# Sensor_Board.net
KiCad netlist of a schematic drawn in Altium Designer
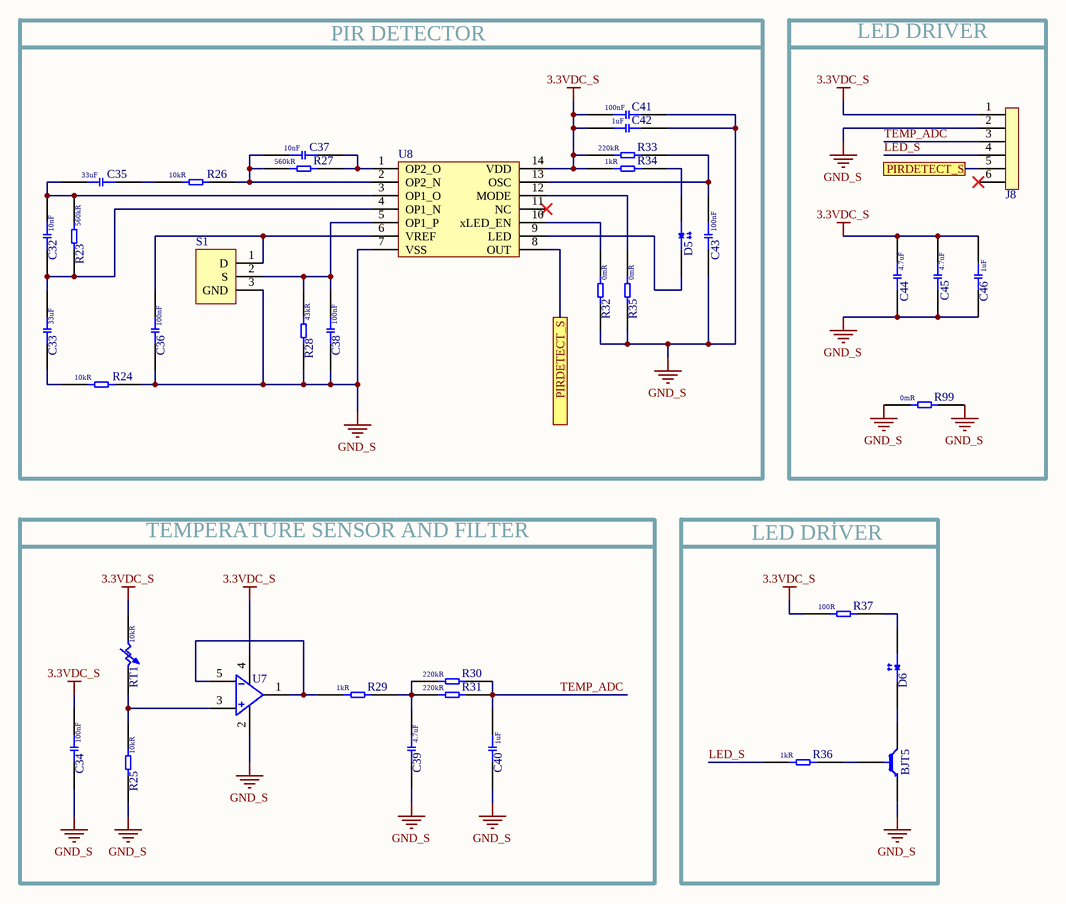
[diagram p0: Sensor Board.SchDoc]

(export (version "E")
  (design (tool "Eeschema 10.0.6"))
  (components
    (comp (ref "BJT5")
      (value "MMBT3904-7-F")
      (footprint "SOT-23F")
      (description "TRANS NPN 40V 0.2A SMD SOT23-3")
      (fields (field (name "MANUFACTURER") "Diodes Zetex") (field (name "DESIGNED BY") "M.C"))
      (libsource (lib "HedefPro_Library") (part "MMBT3904-7-F"))
    )
    (comp (ref "C32")
      (value "0603B103K500CT")
      (footprint "CAP_0603")
      (description "WALSIN - 0603B103K500CT - CAP, 0.01µF, 50V, 10%, X7R, 0603")
      (fields
        (field (name "MANUFACTURER") "Walsin Technologies")
        (field (name "TOLERANCE") "10%")
        (field (name "CAPACITANCE") "10nF")
        (field (name "DESIGNED BY") "M.C")
      )
      (libsource (lib "HedefPro_Library") (part "CAP 10nF 0603"))
    )
    (comp (ref "C33")
      (value "C3216X5R1E336M160AC")
      (footprint "CAP_1206")
      (description "Cap Ceramic 33uF 25V X5R 20% SMD 1206 85C T/R")
      (fields
        (field (name "MANUFACTURER") "TDK")
        (field (name "TOLERANCE") "20%")
        (field (name "CAPACITANCE") "33uF")
        (field (name "DESIGNED BY") "M.C")
      )
      (libsource (lib "HedefPro_Library") (part "CAP  33uF 1206"))
    )
    (comp (ref "C34")
      (value "C0603C104K5RACTU")
      (footprint "CAP_0603")
      (description "Multilayer Ceramic Capacitors (MLCC) - SMD/SMT 50volts 0.1uF X7R 10%")
      (fields
        (field (name "MANUFACTURER") "KEMET")
        (field (name "TOLERANCE") "10%")
        (field (name "CAPACITANCE") "100nF")
        (field (name "DESIGNED BY") "M.C")
      )
      (libsource (lib "HedefPro_Library") (part "CAP 100nF 0603"))
    )
    (comp (ref "C35")
      (value "C3216X5R1E336M160AC")
      (footprint "CAP_1206")
      (description "Cap Ceramic 33uF 25V X5R 20% SMD 1206 85C T/R")
      (fields
        (field (name "MANUFACTURER") "TDK")
        (field (name "TOLERANCE") "20%")
        (field (name "CAPACITANCE") "33uF")
        (field (name "DESIGNED BY") "M.C")
      )
      (libsource (lib "HedefPro_Library") (part "CAP  33uF 1206"))
    )
    (comp (ref "C36")
      (value "ALA7DF471CF450")
      (footprint "CAP_0603")
      (description "CAP CER 100nF %10 0603 SMD")
      (fields
        (field (name "MANUFACTURER") "KEMET")
        (field (name "CAPATICANTE") "100nF")
        (field (name "DESIGNED BY") "M.C")
      )
      (libsource (lib "HedefPro_Library") (part "CAP 100nf 0603_1"))
    )
    (comp (ref "C37")
      (value "0603B103K500CT")
      (footprint "CAP_0603")
      (description "WALSIN - 0603B103K500CT - CAP, 0.01µF, 50V, 10%, X7R, 0603")
      (fields
        (field (name "MANUFACTURER") "Walsin Technologies")
        (field (name "TOLERANCE") "10%")
        (field (name "CAPACITANCE") "10nF")
        (field (name "DESIGNED BY") "M.C")
      )
      (libsource (lib "HedefPro_Library") (part "CAP 10nF 0603"))
    )
    (comp (ref "C38")
      (value "ALA7DF471CF450")
      (footprint "CAP_0603")
      (description "CAP CER 100nF %10 0603 SMD")
      (fields
        (field (name "MANUFACTURER") "KEMET")
        (field (name "CAPATICANTE") "100nF")
        (field (name "DESIGNED BY") "M.C")
      )
      (libsource (lib "HedefPro_Library") (part "CAP 100nf 0603_1"))
    )
    (comp (ref "C39")
      (value "CL21A475KAQNNNE")
      (footprint "CAP_0805")
      (fields
        (field (name "MANUFACTURER") "Samsung")
        (field (name "TOLERANCE") "10%")
        (field (name "CAPACITANCE") "4.7uF")
        (field (name "DESIGNED BY") "M.C")
      )
      (libsource (lib "HedefPro_Library") (part "CAP 4.7uF 0805"))
    )
    (comp (ref "C40")
      (value "CL21B105KBFNNNE")
      (footprint "CAP_0805")
      (fields
        (field (name "MANUFACTURER") "Samsung")
        (field (name "TOLERANCE") "10%")
        (field (name "VOLTAGE") "50V")
        (field (name "CAPACITANCE") "1uF")
        (field (name "DESIGNED BY") "M.C")
      )
      (libsource (lib "HedefPro_Library") (part "CAP 1uF 0805"))
    )
    (comp (ref "C41")
      (value "ALA7DF471CF450")
      (footprint "CAP_0603")
      (description "CAP CER 100nF %10 0603 SMD")
      (fields
        (field (name "MANUFACTURER") "KEMET")
        (field (name "CAPATICANTE") "100nF")
        (field (name "DESIGNED BY") "M.C")
      )
      (libsource (lib "HedefPro_Library") (part "CAP 100nf 0603_1"))
    )
    (comp (ref "C42")
      (value "CL21B105KBFNNNE")
      (footprint "CAP_0805")
      (fields
        (field (name "MANUFACTURER") "Samsung")
        (field (name "TOLERANCE") "10%")
        (field (name "VOLTAGE") "50V")
        (field (name "CAPACITANCE") "1uF")
        (field (name "DESIGNED BY") "M.C")
      )
      (libsource (lib "HedefPro_Library") (part "CAP 1uF 0805"))
    )
    (comp (ref "C43")
      (value "ALA7DF471CF450")
      (footprint "CAP_0603")
      (description "CAP CER 100nF %10 0603 SMD")
      (fields
        (field (name "MANUFACTURER") "KEMET")
        (field (name "CAPATICANTE") "100nF")
        (field (name "DESIGNED BY") "M.C")
      )
      (libsource (lib "HedefPro_Library") (part "CAP 100nf 0603_1"))
    )
    (comp (ref "C44")
      (value "CL21A475KAQNNNE")
      (footprint "CAP_0805")
      (fields
        (field (name "MANUFACTURER") "Samsung")
        (field (name "TOLERANCE") "10%")
        (field (name "CAPACITANCE") "4.7uF")
        (field (name "DESIGNED BY") "M.C")
      )
      (libsource (lib "HedefPro_Library") (part "CAP 4.7uF 0805"))
    )
    (comp (ref "C45")
      (value "CL21A475KAQNNNE")
      (footprint "CAP_0805")
      (fields
        (field (name "MANUFACTURER") "Samsung")
        (field (name "TOLERANCE") "10%")
        (field (name "CAPACITANCE") "4.7uF")
        (field (name "DESIGNED BY") "M.C")
      )
      (libsource (lib "HedefPro_Library") (part "CAP 4.7uF 0805"))
    )
    (comp (ref "C46")
      (value "CL21B105KBFNNNE")
      (footprint "CAP_0805")
      (fields
        (field (name "MANUFACTURER") "Samsung")
        (field (name "TOLERANCE") "10%")
        (field (name "VOLTAGE") "50V")
        (field (name "CAPACITANCE") "1uF")
        (field (name "DESIGNED BY") "M.C")
      )
      (libsource (lib "HedefPro_Library") (part "CAP 1uF 0805"))
    )
    (comp (ref "D5")
      (value "LTST-C171GKT")
      (footprint "LED_0805_GREEN")
      (description "Green 0805 130 º Min 5 mcd Typical 12 mcd Water Clear Lens SMT LED")
      (fields (field (name "MANUFACTURER") "Vishay Lite-On") (field (name "DESIGNED BY") "M.C"))
      (libsource (lib "HedefPro_Library") (part "LTST-C171GKT"))
    )
    (comp (ref "D6")
      (value "LH R974-LP-1-0-20-R18")
      (footprint "LED_0805_RED")
      (description "Single Color LED, Hyper Red, Colorless Diffused, 1.3mm")
      (fields
        (field (name "MANUFACTURER") "Osram Opto")
        (field (name "MANUFACTURER PART NUMBER") "LHR974-LP-1-0-20-R18")
        (field (name "DESIGNED BY") "M.C")
      )
      (libsource (lib "HedefPro_Library") (part "LH R974-LP-1-0-20-R18"))
    )
    (comp (ref "J8")
      (value "64800611622")
      (footprint "64800611622")
      (description "1.50mm 6PIN Connector")
      (fields (field (name "MANUFACTURER") "Wurth Electronics") (field (name "DESIGNED BY") "M.C"))
      (libsource (lib "HedefPro_Library") (part "64800611622"))
    )
    (comp (ref "R23")
      (value "RC0603JR-07560KL")
      (footprint "RES_0603")
      (description "RES SMD 560K OHM 5% 1/10W 0603")
      (fields
        (field (name "MANUFACTURER") "Yageo")
        (field (name "TOLERANCE") "5%")
        (field (name "RESISTANCE") "560kR")
        (field (name "DESIGNED BY") "M.C")
      )
      (libsource (lib "HedefPro_Library") (part "RES 560kR OHM 0603"))
    )
    (comp (ref "R24")
      (value "RC0201FR-0710KL")
      (footprint "RES_0603")
      (description "GENERAL 0201 11% REEL (7INCH)")
      (fields
        (field (name "MANUFACTURER") "Yageo")
        (field (name "TOLERANCE") "1%")
        (field (name "RESISTANCE") "10kR")
        (field (name "DESIGNED BY") "M.C")
      )
      (libsource (lib "HedefPro_Library") (part "RES 10K OHM 0603"))
    )
    (comp (ref "R25")
      (value "RC0201FR-0710KL")
      (footprint "RES_0603")
      (description "GENERAL 0201 11% REEL (7INCH)")
      (fields
        (field (name "MANUFACTURER") "Yageo")
        (field (name "TOLERANCE") "1%")
        (field (name "RESISTANCE") "10kR")
        (field (name "DESIGNED BY") "M.C")
      )
      (libsource (lib "HedefPro_Library") (part "RES 10K OHM 0603"))
    )
    (comp (ref "R26")
      (value "RC0201FR-0710KL")
      (footprint "RES_0603")
      (description "GENERAL 0201 11% REEL (7INCH)")
      (fields
        (field (name "MANUFACTURER") "Yageo")
        (field (name "TOLERANCE") "1%")
        (field (name "RESISTANCE") "10kR")
        (field (name "DESIGNED BY") "M.C")
      )
      (libsource (lib "HedefPro_Library") (part "RES 10K OHM 0603"))
    )
    (comp (ref "R27")
      (value "RC0603JR-07560KL")
      (footprint "RES_0603")
      (description "RES SMD 560K OHM 5% 1/10W 0603")
      (fields
        (field (name "MANUFACTURER") "Yageo")
        (field (name "TOLERANCE") "5%")
        (field (name "RESISTANCE") "560kR")
        (field (name "DESIGNED BY") "M.C")
      )
      (libsource (lib "HedefPro_Library") (part "RES 560kR OHM 0603"))
    )
    (comp (ref "R28")
      (value "RC0603JR-0743KL")
      (footprint "RES_0603")
      (fields
        (field (name "MANUFACTURER") "Yageo")
        (field (name "TOLERANCE") "5%")
        (field (name "RESISTANCE") "43kR")
        (field (name "DESIGNED BY") "M.C")
      )
      (libsource (lib "HedefPro_Library") (part "RES 43kR OHM 0603"))
    )
    (comp (ref "R29")
      (value "RC0603FR-101KL")
      (footprint "RES_0603")
      (description "Res Thick Film 0603 1K Ohm 1% 0.1W(1/10W) ±100ppm/C Pad SMD T/R")
      (fields
        (field (name "MANUFACTURER") "Yageo")
        (field (name "TOLERANCE") "1%")
        (field (name "RESISTANCE") "1kR")
        (field (name "DESIGNED BY") "M.C")
      )
      (libsource (lib "HedefPro_Library") (part "RES 1kR OHM 0603"))
    )
    (comp (ref "R30")
      (value "RC0603JR-07220KL")
      (footprint "RES_0603")
      (fields
        (field (name "MANUFACTURER") "Yageo")
        (field (name "TOLERANCE") "5%")
        (field (name "RESISTANCE") "220kR")
        (field (name "DESIGNED BY") "M.C")
      )
      (libsource (lib "HedefPro_Library") (part "RES 220kR OHM 0603"))
    )
    (comp (ref "R31")
      (value "RC0603JR-07220KL")
      (footprint "RES_0603")
      (fields
        (field (name "MANUFACTURER") "Yageo")
        (field (name "TOLERANCE") "5%")
        (field (name "RESISTANCE") "220kR")
        (field (name "DESIGNED BY") "M.C")
      )
      (libsource (lib "HedefPro_Library") (part "RES 220kR OHM 0603"))
    )
    (comp (ref "R32")
      (value "RC0603JR-070RL")
      (footprint "RES_0603")
      (description "RES SMD 0 OHM JUMPER 1/10W 0603")
      (fields
        (field (name "MANUFACTURER") "Yageo")
        (field (name "TOLERANCE") "1%")
        (field (name "RESISTANCE") "0mR")
        (field (name "DESIGNED BY") "M.C")
      )
      (libsource (lib "HedefPro_Library") (part "RES 0mR OHM 0603"))
    )
    (comp (ref "R33")
      (value "RC0603JR-07220KL")
      (footprint "RES_0603")
      (fields
        (field (name "MANUFACTURER") "Yageo")
        (field (name "TOLERANCE") "5%")
        (field (name "RESISTANCE") "220kR")
        (field (name "DESIGNED BY") "M.C")
      )
      (libsource (lib "HedefPro_Library") (part "RES 220kR OHM 0603"))
    )
    (comp (ref "R34")
      (value "RC0603FR-101KL")
      (footprint "RES_0603")
      (description "Res Thick Film 0603 1K Ohm 1% 0.1W(1/10W) ±100ppm/C Pad SMD T/R")
      (fields
        (field (name "MANUFACTURER") "Yageo")
        (field (name "TOLERANCE") "1%")
        (field (name "RESISTANCE") "1kR")
        (field (name "DESIGNED BY") "M.C")
      )
      (libsource (lib "HedefPro_Library") (part "RES 1kR OHM 0603"))
    )
    (comp (ref "R35")
      (value "RC0603JR-070RL")
      (footprint "RES_0603")
      (description "RES SMD 0 OHM JUMPER 1/10W 0603")
      (fields
        (field (name "MANUFACTURER") "Yageo")
        (field (name "TOLERANCE") "1%")
        (field (name "RESISTANCE") "0mR")
        (field (name "DESIGNED BY") "M.C")
      )
      (libsource (lib "HedefPro_Library") (part "RES 0mR OHM 0603"))
    )
    (comp (ref "R36")
      (value "RC0603FR-101KL")
      (footprint "RES_0603")
      (description "Res Thick Film 0603 1K Ohm 1% 0.1W(1/10W) ±100ppm/C Pad SMD T/R")
      (fields
        (field (name "MANUFACTURER") "Yageo")
        (field (name "TOLERANCE") "1%")
        (field (name "RESISTANCE") "1kR")
        (field (name "DESIGNED BY") "M.C")
      )
      (libsource (lib "HedefPro_Library") (part "RES 1kR OHM 0603"))
    )
    (comp (ref "R37")
      (value "RC0603JR-07100RL")
      (footprint "RES_0603")
      (description "Res Thick Film 0603 100 Ohm 5% 0.1W(1/10W) ±100ppm/C Molded SMD Paper T/R")
      (fields
        (field (name "MANUFACTURER") "Yageo")
        (field (name "TOLERANCE") "5%")
        (field (name "RESISTANCE") "100R")
        (field (name "DESIGNED BY") "M.C")
      )
      (libsource (lib "HedefPro_Library") (part "RES 100R OHM 0603"))
    )
    (comp (ref "R99")
      (value "RC0603JR-070RL")
      (footprint "RES_0603")
      (description "RES SMD 0 OHM JUMPER 1/10W 0603")
      (fields
        (field (name "MANUFACTURER") "Yageo")
        (field (name "TOLERANCE") "1%")
        (field (name "RESISTANCE") "0mR")
        (field (name "DESIGNED BY") "M.C")
      )
      (libsource (lib "HedefPro_Library") (part "RES 0mR OHM 0603"))
    )
    (comp (ref "RT1")
      (value "TFPT1206L1002FM")
      (footprint "RES_1206")
      (description "Thermistor PTC 10K Ohm 1% 2-Pin 1206 Surface Mount Solder Pad T/R Automotive")
      (fields
        (field (name "MANUFACTURER") "Vishay Dale")
        (field (name "TOLERANCE") "1%")
        (field (name "RESISTANCE") "10kR")
        (field (name "DESIGNED BY") "M.C")
      )
      (libsource (lib "HedefPro_Library") (part "TFPT1206L1002FM"))
    )
    (comp (ref "S1")
      (value "LHI 878/3902")
      (footprint "LHI 878/3902 - PYD 1388 / 708")
      (description "PYD 1388 / 7083 SENSOR PYRO DETECTOR DUAL MOTION")
      (fields
        (field (name "MANUFACTURER") "Excelitas")
        (field (name "MANUFACTURER PART NUMBER") "LHI878/3902")
        (field (name "DESIGNED BY") "M.C")
      )
      (libsource (lib "HedefPro_Library") (part "LHI 878/3902"))
    )
    (comp (ref "U7")
      (value "OPA314AIDBVR")
      (footprint "SOT23-5")
      (description "Op Amp")
      (fields (field (name "MANUFACTURER") "Texas Instruments") (field (name "DESIGNED BY") "M.C"))
      (libsource (lib "HedefPro_Library") (part "OPA314AIDBVR"))
    )
    (comp (ref "U8")
      (value "NCS36000DRG")
      (footprint "SOIC14")
      (description "Low Noise Amplifiers and LDO Regulator 14-Pin SOIC N T/R")
      (fields (field (name "MANUFACTURER") "ON Semiconductor") (field (name "DESIGNED BY") "M.C"))
      (libsource (lib "HedefPro_Library") (part "NCS36000DRG"))
    )
  )
  (nets
    (net (code "1") (name "/LED_S") (class "Default")
      (node (ref "J8") (pin "4") (pinfunction "4_4") (pintype "passive"))
      (node (ref "R36") (pin "1") (pinfunction "1_1") (pintype "passive"))
    )
    (net (code "2") (name "/PIRDETECT_S") (class "Default")
      (node (ref "J8") (pin "5") (pinfunction "5_5") (pintype "passive"))
      (node (ref "U8") (pin "8") (pinfunction "OUT_8") (pintype "passive"))
    )
    (net (code "3") (name "/TEMP_ADC") (class "Default")
      (node (ref "C40") (pin "2") (pinfunction "2_2") (pintype "passive"))
      (node (ref "J8") (pin "3") (pinfunction "3_3") (pintype "passive"))
      (node (ref "R30") (pin "2") (pinfunction "2_2") (pintype "passive"))
      (node (ref "R31") (pin "2") (pinfunction "2_2") (pintype "passive"))
    )
    (net (code "4") (name "3.3VDC_S") (class "Default")
      (node (ref "C34") (pin "2") (pinfunction "2_2") (pintype "passive"))
      (node (ref "C41") (pin "2") (pinfunction "2_2") (pintype "passive"))
      (node (ref "C42") (pin "2") (pinfunction "2_2") (pintype "passive"))
      (node (ref "C44") (pin "2") (pinfunction "2_2") (pintype "passive"))
      (node (ref "C45") (pin "2") (pinfunction "2_2") (pintype "passive"))
      (node (ref "C46") (pin "2") (pinfunction "2_2") (pintype "passive"))
      (node (ref "J8") (pin "1") (pinfunction "1_1") (pintype "passive"))
      (node (ref "R33") (pin "2") (pinfunction "2_2") (pintype "passive"))
      (node (ref "R34") (pin "2") (pinfunction "2_2") (pintype "passive"))
      (node (ref "R37") (pin "2") (pinfunction "2_2") (pintype "passive"))
      (node (ref "RT1") (pin "1") (pinfunction "1_1") (pintype "passive"))
      (node (ref "U7") (pin "4") (pinfunction "V+_4") (pintype "passive"))
      (node (ref "U8") (pin "14") (pinfunction "VDD_14") (pintype "passive"))
    )
    (net (code "5") (name "GND_S") (class "Default")
      (node (ref "BJT5") (pin "2") (pinfunction "E_2") (pintype "passive"))
      (node (ref "C34") (pin "1") (pinfunction "1_1") (pintype "passive"))
      (node (ref "C36") (pin "1") (pinfunction "1_1") (pintype "passive"))
      (node (ref "C38") (pin "1") (pinfunction "1_1") (pintype "passive"))
      (node (ref "C39") (pin "1") (pinfunction "1_1") (pintype "passive"))
      (node (ref "C40") (pin "1") (pinfunction "1_1") (pintype "passive"))
      (node (ref "C41") (pin "1") (pinfunction "1_1") (pintype "passive"))
      (node (ref "C42") (pin "1") (pinfunction "1_1") (pintype "passive"))
      (node (ref "C43") (pin "1") (pinfunction "1_1") (pintype "passive"))
      (node (ref "C44") (pin "1") (pinfunction "1_1") (pintype "passive"))
      (node (ref "C45") (pin "1") (pinfunction "1_1") (pintype "passive"))
      (node (ref "C46") (pin "1") (pinfunction "1_1") (pintype "passive"))
      (node (ref "J8") (pin "2") (pinfunction "2_2") (pintype "passive"))
      (node (ref "R24") (pin "1") (pinfunction "1_1") (pintype "passive"))
      (node (ref "R25") (pin "1") (pinfunction "1_1") (pintype "passive"))
      (node (ref "R28") (pin "1") (pinfunction "1_1") (pintype "passive"))
      (node (ref "R32") (pin "1") (pinfunction "1_1") (pintype "passive"))
      (node (ref "R35") (pin "1") (pinfunction "1_1") (pintype "passive"))
      (node (ref "R99") (pin "1") (pinfunction "1_1") (pintype "passive"))
      (node (ref "R99") (pin "2") (pinfunction "2_2") (pintype "passive"))
      (node (ref "S1") (pin "3") (pinfunction "GND_3") (pintype "passive"))
      (node (ref "U7") (pin "2") (pinfunction "V-_2") (pintype "passive"))
      (node (ref "U8") (pin "7") (pinfunction "VSS_7") (pintype "passive"))
    )
    (net (code "6") (name "Net-(BJT5-B)") (class "Default")
      (node (ref "BJT5") (pin "1") (pinfunction "B_1") (pintype "passive"))
      (node (ref "R36") (pin "2") (pinfunction "2_2") (pintype "passive"))
    )
    (net (code "7") (name "Net-(BJT5-C)") (class "Default")
      (node (ref "BJT5") (pin "3") (pinfunction "C_3") (pintype "passive"))
      (node (ref "D6") (pin "1") (pinfunction "1_1") (pintype "passive"))
    )
    (net (code "8") (name "Net-(C33-Pad2)") (class "Default")
      (node (ref "C33") (pin "2") (pinfunction "2_2") (pintype "passive"))
      (node (ref "R24") (pin "2") (pinfunction "2_2") (pintype "passive"))
    )
    (net (code "9") (name "Net-(C35-Pad2)") (class "Default")
      (node (ref "C35") (pin "2") (pinfunction "2_2") (pintype "passive"))
      (node (ref "R26") (pin "1") (pinfunction "1_1") (pintype "passive"))
    )
    (net (code "10") (name "Net-(C39-Pad2)") (class "Default")
      (node (ref "C39") (pin "2") (pinfunction "2_2") (pintype "passive"))
      (node (ref "R29") (pin "2") (pinfunction "2_2") (pintype "passive"))
      (node (ref "R30") (pin "1") (pinfunction "1_1") (pintype "passive"))
      (node (ref "R31") (pin "1") (pinfunction "1_1") (pintype "passive"))
    )
    (net (code "11") (name "Net-(D5-Pad2)") (class "Default")
      (node (ref "D5") (pin "2") (pinfunction "2_2") (pintype "passive"))
      (node (ref "R34") (pin "1") (pinfunction "1_1") (pintype "passive"))
    )
    (net (code "12") (name "Net-(D6-Pad2)") (class "Default")
      (node (ref "D6") (pin "2") (pinfunction "2_2") (pintype "passive"))
      (node (ref "R37") (pin "1") (pinfunction "1_1") (pintype "passive"))
    )
    (net (code "13") (name "Net-(S1-D)") (class "Default")
      (node (ref "C36") (pin "2") (pinfunction "2_2") (pintype "passive"))
      (node (ref "S1") (pin "1") (pinfunction "D_1") (pintype "passive"))
      (node (ref "U8") (pin "6") (pinfunction "VREF_6") (pintype "passive"))
    )
    (net (code "14") (name "Net-(S1-S)") (class "Default")
      (node (ref "C38") (pin "2") (pinfunction "2_2") (pintype "passive"))
      (node (ref "R28") (pin "2") (pinfunction "2_2") (pintype "passive"))
      (node (ref "S1") (pin "2") (pinfunction "S_2") (pintype "passive"))
      (node (ref "U8") (pin "5") (pinfunction "OP1_P_5") (pintype "passive"))
    )
    (net (code "15") (name "Net-(U7-+IN)") (class "Default")
      (node (ref "R25") (pin "2") (pinfunction "2_2") (pintype "passive"))
      (node (ref "RT1") (pin "2") (pinfunction "2_2") (pintype "passive"))
      (node (ref "U7") (pin "3") (pinfunction "+IN_3") (pintype "passive"))
    )
    (net (code "16") (name "Net-(U7--IN)") (class "Default")
      (node (ref "R29") (pin "1") (pinfunction "1_1") (pintype "passive"))
      (node (ref "U7") (pin "1") (pinfunction "OUT_1") (pintype "passive"))
      (node (ref "U7") (pin "5") (pinfunction "-IN_5") (pintype "passive"))
    )
    (net (code "17") (name "Net-(U8-LED)") (class "Default")
      (node (ref "D5") (pin "1") (pinfunction "1_1") (pintype "passive"))
      (node (ref "U8") (pin "9") (pinfunction "LED_9") (pintype "passive"))
    )
    (net (code "18") (name "Net-(U8-MODE)") (class "Default")
      (node (ref "R35") (pin "2") (pinfunction "2_2") (pintype "passive"))
      (node (ref "U8") (pin "12") (pinfunction "MODE_12") (pintype "passive"))
    )
    (net (code "19") (name "Net-(U8-OP1_N)") (class "Default")
      (node (ref "C32") (pin "1") (pinfunction "1_1") (pintype "passive"))
      (node (ref "C33") (pin "1") (pinfunction "1_1") (pintype "passive"))
      (node (ref "R23") (pin "1") (pinfunction "1_1") (pintype "passive"))
      (node (ref "U8") (pin "4") (pinfunction "OP1_N_4") (pintype "passive"))
    )
    (net (code "20") (name "Net-(U8-OP1_O)") (class "Default")
      (node (ref "C32") (pin "2") (pinfunction "2_2") (pintype "passive"))
      (node (ref "C35") (pin "1") (pinfunction "1_1") (pintype "passive"))
      (node (ref "R23") (pin "2") (pinfunction "2_2") (pintype "passive"))
      (node (ref "U8") (pin "3") (pinfunction "OP1_O_3") (pintype "passive"))
    )
    (net (code "21") (name "Net-(U8-OP2_N)") (class "Default")
      (node (ref "C37") (pin "1") (pinfunction "1_1") (pintype "passive"))
      (node (ref "R26") (pin "2") (pinfunction "2_2") (pintype "passive"))
      (node (ref "R27") (pin "1") (pinfunction "1_1") (pintype "passive"))
      (node (ref "U8") (pin "2") (pinfunction "OP2_N_2") (pintype "passive"))
    )
    (net (code "22") (name "Net-(U8-OP2_O)") (class "Default")
      (node (ref "C37") (pin "2") (pinfunction "2_2") (pintype "passive"))
      (node (ref "R27") (pin "2") (pinfunction "2_2") (pintype "passive"))
      (node (ref "U8") (pin "1") (pinfunction "OP2_O_1") (pintype "passive"))
    )
    (net (code "23") (name "Net-(U8-OSC)") (class "Default")
      (node (ref "C43") (pin "2") (pinfunction "2_2") (pintype "passive"))
      (node (ref "R33") (pin "1") (pinfunction "1_1") (pintype "passive"))
      (node (ref "U8") (pin "13") (pinfunction "OSC_13") (pintype "passive"))
    )
    (net (code "24") (name "Net-(U8-xLED_EN)") (class "Default")
      (node (ref "R32") (pin "2") (pinfunction "2_2") (pintype "passive"))
      (node (ref "U8") (pin "10") (pinfunction "xLED_EN_10") (pintype "passive"))
    )
    (net (code "25") (name "unconnected-(J8-Pad6)") (class "Default")
      (node (ref "J8") (pin "6") (pinfunction "6_6") (pintype "passive+no_connect"))
    )
    (net (code "26") (name "unconnected-(U8-NC-Pad11)") (class "Default")
      (node (ref "U8") (pin "11") (pinfunction "NC_11") (pintype "passive+no_connect"))
    )
  )
)
